# CamLink.net
KiCad netlist of a schematic drawn in Altium Designer
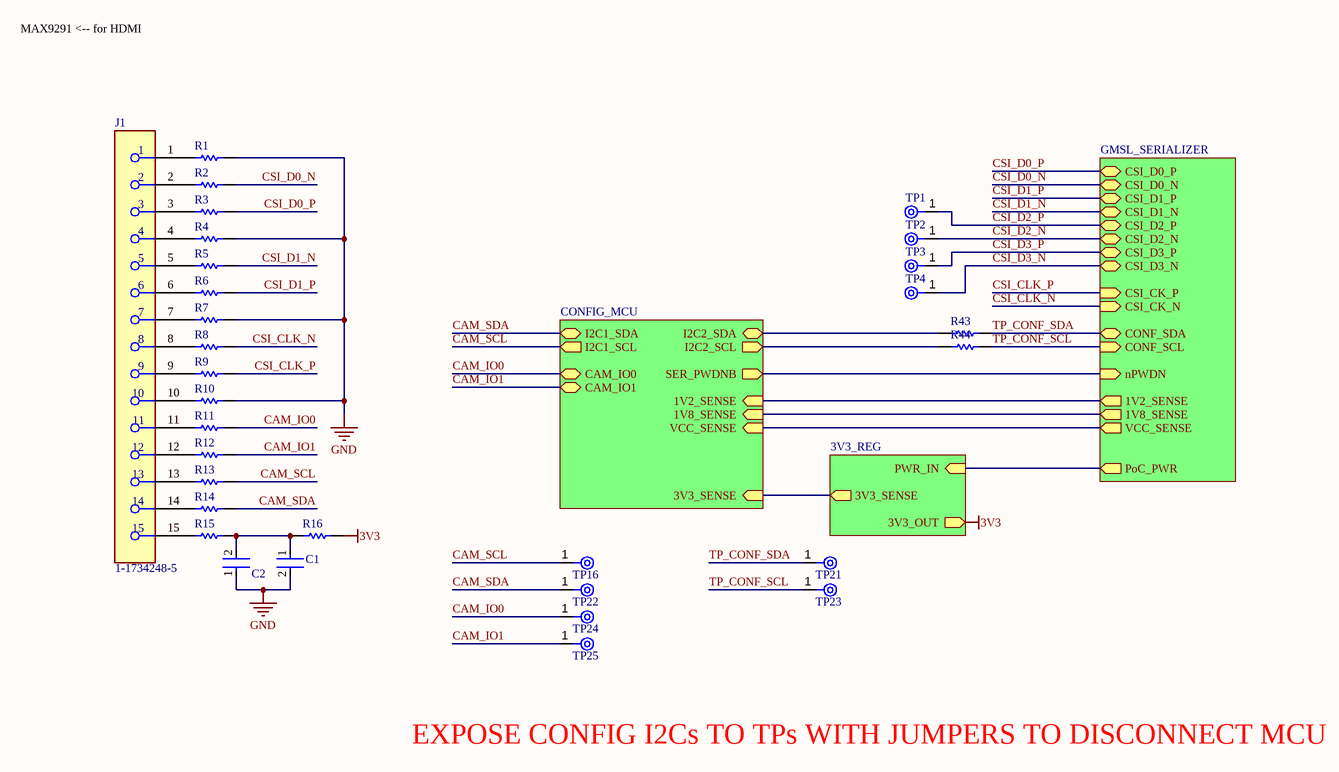
[diagram p0: CamLink.SchDoc]

(export (version "E")
  (design (tool "Eeschema 10.0.6"))
  (components
    (comp (ref "C1")
      (value "CL05A106MP5NUNC")
      (footprint "FP-CL05A106MP5NUNC-MFG")
      (description "CAP CER 10UF 10V X5R 0402")
      (fields
        (field (name "OCTOPART") "https://octopart.com/cl05a106mp5nunc-samsung-22457395")
        (field (name "TOLERANCE") "20%")
      )
      (libsource (lib "Altium Content Vault") (part "b4654b650e69147ec39a6b967a45e02"))
    )
    (comp (ref "C2")
      (value "C1005X7R1H104K050BB")
      (footprint "FP-C1005-050-0_05-IPC_C")
      (description "Multilayer Ceramic Capacitors 100nF ±10% 50V X7R SMD 0402")
      (fields (field (name "VOLTAGE") "50V") (field (name "TOLERANCE") "10%"))
      (libsource (lib "Altium Content Vault") (part "b4654b650e69147ec39a6b967a45e02"))
    )
    (comp (ref "J1")
      (value "1-1734248-5")
      (footprint "FP-1-1734248-5-MFG")
      (description "CONN FPC VERT 15POS 1.00MM SMD")
      (fields
        (field (name "MANUFACTURER") "TE")
        (field (name "OCTOPART") "https://octopart.com/1-1734248-5-te+connectivity-40620898")
      )
      (libsource (lib "Altium Content Vault") (part "a0777be16b290adccad2a8f9338c195"))
    )
    (comp (ref "R1")
      (value "RC0402JR-070RL")
      (footprint "RESC1005X40X25NL05T10")
      (fields (field (name "MANUFACTURER") "Yageo / Phycomp"))
      (libsource (lib "Altium Content Vault") (part "RES"))
    )
    (comp (ref "R2")
      (value "RC0402JR-070RL")
      (footprint "RESC1005X40X25NL05T10")
      (fields (field (name "MANUFACTURER") "Yageo / Phycomp"))
      (libsource (lib "Altium Content Vault") (part "RES"))
    )
    (comp (ref "R3")
      (value "RC0402JR-070RL")
      (footprint "RESC1005X40X25NL05T10")
      (fields (field (name "MANUFACTURER") "Yageo / Phycomp"))
      (libsource (lib "Altium Content Vault") (part "RES"))
    )
    (comp (ref "R4")
      (value "RC0402JR-070RL")
      (footprint "RESC1005X40X25NL05T10")
      (fields (field (name "MANUFACTURER") "Yageo / Phycomp"))
      (libsource (lib "Altium Content Vault") (part "RES"))
    )
    (comp (ref "R5")
      (value "RC0402JR-070RL")
      (footprint "RESC1005X40X25NL05T10")
      (fields (field (name "MANUFACTURER") "Yageo / Phycomp"))
      (libsource (lib "Altium Content Vault") (part "RES"))
    )
    (comp (ref "R6")
      (value "RC0402JR-070RL")
      (footprint "RESC1005X40X25NL05T10")
      (fields (field (name "MANUFACTURER") "Yageo / Phycomp"))
      (libsource (lib "Altium Content Vault") (part "RES"))
    )
    (comp (ref "R7")
      (value "RC0402JR-070RL")
      (footprint "RESC1005X40X25NL05T10")
      (fields (field (name "MANUFACTURER") "Yageo / Phycomp"))
      (libsource (lib "Altium Content Vault") (part "RES"))
    )
    (comp (ref "R8")
      (value "RC0402JR-070RL")
      (footprint "RESC1005X40X25NL05T10")
      (fields (field (name "MANUFACTURER") "Yageo / Phycomp"))
      (libsource (lib "Altium Content Vault") (part "RES"))
    )
    (comp (ref "R9")
      (value "RC0402JR-070RL")
      (footprint "RESC1005X40X25NL05T10")
      (fields (field (name "MANUFACTURER") "Yageo / Phycomp"))
      (libsource (lib "Altium Content Vault") (part "RES"))
    )
    (comp (ref "R10")
      (value "RC0402JR-070RL")
      (footprint "RESC1005X40X25NL05T10")
      (fields (field (name "MANUFACTURER") "Yageo / Phycomp"))
      (libsource (lib "Altium Content Vault") (part "RES"))
    )
    (comp (ref "R11")
      (value "RC0402JR-070RL")
      (footprint "RESC1005X40X25NL05T10")
      (fields (field (name "MANUFACTURER") "Yageo / Phycomp"))
      (libsource (lib "Altium Content Vault") (part "RES"))
    )
    (comp (ref "R12")
      (value "RC0402JR-070RL")
      (footprint "RESC1005X40X25NL05T10")
      (fields (field (name "MANUFACTURER") "Yageo / Phycomp"))
      (libsource (lib "Altium Content Vault") (part "RES"))
    )
    (comp (ref "R13")
      (value "RC0402JR-070RL")
      (footprint "RESC1005X40X25NL05T10")
      (fields (field (name "MANUFACTURER") "Yageo / Phycomp"))
      (libsource (lib "Altium Content Vault") (part "RES"))
    )
    (comp (ref "R14")
      (value "RC0402JR-070RL")
      (footprint "RESC1005X40X25NL05T10")
      (fields (field (name "MANUFACTURER") "Yageo / Phycomp"))
      (libsource (lib "Altium Content Vault") (part "RES"))
    )
    (comp (ref "R15")
      (value "RC0402JR-070RL")
      (footprint "RESC1005X40X25NL05T10")
      (fields (field (name "MANUFACTURER") "Yageo / Phycomp"))
      (libsource (lib "Altium Content Vault") (part "RES"))
    )
    (comp (ref "R16")
      (value "RC0402JR-070RL")
      (footprint "RESC1005X40X25NL05T10")
      (fields (field (name "MANUFACTURER") "Yageo / Phycomp"))
      (libsource (lib "Altium Content Vault") (part "RES"))
    )
    (comp (ref "R43")
      (value "RC0402JR-070RL")
      (footprint "RESC1005X40X25NL05T10")
      (fields (field (name "MANUFACTURER") "Yageo / Phycomp"))
      (libsource (lib "Altium Content Vault") (part "RES"))
    )
    (comp (ref "R44")
      (value "RC0402JR-070RL")
      (footprint "RESC1005X40X25NL05T10")
      (fields (field (name "MANUFACTURER") "Yageo / Phycomp"))
      (libsource (lib "Altium Content Vault") (part "RES"))
    )
    (comp (ref "TP1")
      (value "TPAD6R")
      (footprint "New footprint 1")
      (description "Test Point .6mm")
      (libsource (lib "Space Concordia") (part "TP"))
    )
    (comp (ref "TP2")
      (value "TPAD6R")
      (footprint "New footprint 1")
      (description "Test Point .6mm")
      (libsource (lib "Space Concordia") (part "TP"))
    )
    (comp (ref "TP3")
      (value "TPAD6R")
      (footprint "New footprint 1")
      (description "Test Point .6mm")
      (libsource (lib "Space Concordia") (part "TP"))
    )
    (comp (ref "TP4")
      (value "TPAD6R")
      (footprint "New footprint 1")
      (description "Test Point .6mm")
      (libsource (lib "Space Concordia") (part "TP"))
    )
    (comp (ref "TP16")
      (value "TPAD6R")
      (footprint "New footprint 1")
      (description "Test Point .6mm")
      (libsource (lib "Space Concordia") (part "TP"))
    )
    (comp (ref "TP21")
      (value "TPAD6R")
      (footprint "New footprint 1")
      (description "Test Point .6mm")
      (libsource (lib "Space Concordia") (part "TP"))
    )
    (comp (ref "TP22")
      (value "TPAD6R")
      (footprint "New footprint 1")
      (description "Test Point .6mm")
      (libsource (lib "Space Concordia") (part "TP"))
    )
    (comp (ref "TP23")
      (value "TPAD6R")
      (footprint "New footprint 1")
      (description "Test Point .6mm")
      (libsource (lib "Space Concordia") (part "TP"))
    )
    (comp (ref "TP24")
      (value "TPAD6R")
      (footprint "New footprint 1")
      (description "Test Point .6mm")
      (libsource (lib "Space Concordia") (part "TP"))
    )
    (comp (ref "TP25")
      (value "TPAD6R")
      (footprint "New footprint 1")
      (description "Test Point .6mm")
      (libsource (lib "Space Concordia") (part "TP"))
    )
  )
  (nets
    (net (code "4") (name "/CAM_IO0") (class "Default")
      (node (ref "R11") (pin "2") (pinfunction "2_2") (pintype "passive"))
      (node (ref "TP24") (pin "1") (pinfunction "TP_1") (pintype "passive"))
    )
    (net (code "5") (name "/CAM_IO1") (class "Default")
      (node (ref "R12") (pin "2") (pinfunction "2_2") (pintype "passive"))
      (node (ref "TP25") (pin "1") (pinfunction "TP_1") (pintype "passive"))
    )
    (net (code "6") (name "/CAM_SCL") (class "Default")
      (node (ref "R13") (pin "2") (pinfunction "2_2") (pintype "passive"))
      (node (ref "TP16") (pin "1") (pinfunction "TP_1") (pintype "passive"))
    )
    (net (code "7") (name "/CAM_SDA") (class "Default")
      (node (ref "R14") (pin "2") (pinfunction "2_2") (pintype "passive"))
      (node (ref "TP22") (pin "1") (pinfunction "TP_1") (pintype "passive"))
    )
    (net (code "8") (name "/CSI_CLK_N") (class "Default")
      (node (ref "R8") (pin "2") (pinfunction "2_2") (pintype "passive"))
    )
    (net (code "9") (name "/CSI_CLK_P") (class "Default")
      (node (ref "R9") (pin "2") (pinfunction "2_2") (pintype "passive"))
    )
    (net (code "10") (name "/CSI_D0_N") (class "Default")
      (node (ref "R2") (pin "2") (pinfunction "2_2") (pintype "passive"))
    )
    (net (code "11") (name "/CSI_D0_P") (class "Default")
      (node (ref "R3") (pin "2") (pinfunction "2_2") (pintype "passive"))
    )
    (net (code "12") (name "/CSI_D1_N") (class "Default")
      (node (ref "R5") (pin "2") (pinfunction "2_2") (pintype "passive"))
    )
    (net (code "13") (name "/CSI_D1_P") (class "Default")
      (node (ref "R6") (pin "2") (pinfunction "2_2") (pintype "passive"))
    )
    (net (code "14") (name "/CSI_D2_N") (class "Default")
      (node (ref "TP2") (pin "1") (pinfunction "TP_1") (pintype "passive"))
    )
    (net (code "15") (name "/CSI_D2_P") (class "Default")
      (node (ref "TP1") (pin "1") (pinfunction "TP_1") (pintype "passive"))
    )
    (net (code "16") (name "/CSI_D3_N") (class "Default")
      (node (ref "TP4") (pin "1") (pinfunction "TP_1") (pintype "passive"))
    )
    (net (code "17") (name "/CSI_D3_P") (class "Default")
      (node (ref "TP3") (pin "1") (pinfunction "TP_1") (pintype "passive"))
    )
    (net (code "18") (name "/I2C2_SCL") (class "Default")
      (node (ref "R44") (pin "1") (pinfunction "1_1") (pintype "passive"))
    )
    (net (code "19") (name "/I2C2_SDA") (class "Default")
      (node (ref "R43") (pin "1") (pinfunction "1_1") (pintype "passive"))
    )
    (net (code "22") (name "/TP_CONF_SCL") (class "Default")
      (node (ref "R44") (pin "2") (pinfunction "2_2") (pintype "passive"))
      (node (ref "TP23") (pin "1") (pinfunction "TP_1") (pintype "passive"))
    )
    (net (code "23") (name "/TP_CONF_SDA") (class "Default")
      (node (ref "R43") (pin "2") (pinfunction "2_2") (pintype "passive"))
      (node (ref "TP21") (pin "1") (pinfunction "TP_1") (pintype "passive"))
    )
    (net (code "25") (name "3V3") (class "Default")
      (node (ref "R16") (pin "2") (pinfunction "2_2") (pintype "passive"))
    )
    (net (code "26") (name "GND") (class "Default")
      (node (ref "C1") (pin "2") (pinfunction "2_2") (pintype "passive"))
      (node (ref "C2") (pin "1") (pinfunction "1_1") (pintype "passive"))
      (node (ref "R1") (pin "2") (pinfunction "2_2") (pintype "passive"))
      (node (ref "R10") (pin "2") (pinfunction "2_2") (pintype "passive"))
      (node (ref "R4") (pin "2") (pinfunction "2_2") (pintype "passive"))
      (node (ref "R7") (pin "2") (pinfunction "2_2") (pintype "passive"))
    )
    (net (code "27") (name "Net-(C1-Pad1)") (class "Default")
      (node (ref "C1") (pin "1") (pinfunction "1_1") (pintype "passive"))
      (node (ref "C2") (pin "2") (pinfunction "2_2") (pintype "passive"))
      (node (ref "R15") (pin "2") (pinfunction "2_2") (pintype "passive"))
      (node (ref "R16") (pin "1") (pinfunction "1_1") (pintype "passive"))
    )
    (net (code "28") (name "Net-(J1-Pad1)") (class "Default")
      (node (ref "J1") (pin "1") (pinfunction "1_1") (pintype "passive"))
      (node (ref "R1") (pin "1") (pinfunction "1_1") (pintype "passive"))
    )
    (net (code "29") (name "Net-(J1-Pad2)") (class "Default")
      (node (ref "J1") (pin "2") (pinfunction "2_2") (pintype "passive"))
      (node (ref "R2") (pin "1") (pinfunction "1_1") (pintype "passive"))
    )
    (net (code "30") (name "Net-(J1-Pad3)") (class "Default")
      (node (ref "J1") (pin "3") (pinfunction "3_3") (pintype "passive"))
      (node (ref "R3") (pin "1") (pinfunction "1_1") (pintype "passive"))
    )
    (net (code "31") (name "Net-(J1-Pad4)") (class "Default")
      (node (ref "J1") (pin "4") (pinfunction "4_4") (pintype "passive"))
      (node (ref "R4") (pin "1") (pinfunction "1_1") (pintype "passive"))
    )
    (net (code "32") (name "Net-(J1-Pad5)") (class "Default")
      (node (ref "J1") (pin "5") (pinfunction "5_5") (pintype "passive"))
      (node (ref "R5") (pin "1") (pinfunction "1_1") (pintype "passive"))
    )
    (net (code "33") (name "Net-(J1-Pad6)") (class "Default")
      (node (ref "J1") (pin "6") (pinfunction "6_6") (pintype "passive"))
      (node (ref "R6") (pin "1") (pinfunction "1_1") (pintype "passive"))
    )
    (net (code "34") (name "Net-(J1-Pad7)") (class "Default")
      (node (ref "J1") (pin "7") (pinfunction "7_7") (pintype "passive"))
      (node (ref "R7") (pin "1") (pinfunction "1_1") (pintype "passive"))
    )
    (net (code "35") (name "Net-(J1-Pad8)") (class "Default")
      (node (ref "J1") (pin "8") (pinfunction "8_8") (pintype "passive"))
      (node (ref "R8") (pin "1") (pinfunction "1_1") (pintype "passive"))
    )
    (net (code "36") (name "Net-(J1-Pad9)") (class "Default")
      (node (ref "J1") (pin "9") (pinfunction "9_9") (pintype "passive"))
      (node (ref "R9") (pin "1") (pinfunction "1_1") (pintype "passive"))
    )
    (net (code "37") (name "Net-(J1-Pad10)") (class "Default")
      (node (ref "J1") (pin "10") (pinfunction "10_10") (pintype "passive"))
      (node (ref "R10") (pin "1") (pinfunction "1_1") (pintype "passive"))
    )
    (net (code "38") (name "Net-(J1-Pad11)") (class "Default")
      (node (ref "J1") (pin "11") (pinfunction "11_11") (pintype "passive"))
      (node (ref "R11") (pin "1") (pinfunction "1_1") (pintype "passive"))
    )
    (net (code "39") (name "Net-(J1-Pad12)") (class "Default")
      (node (ref "J1") (pin "12") (pinfunction "12_12") (pintype "passive"))
      (node (ref "R12") (pin "1") (pinfunction "1_1") (pintype "passive"))
    )
    (net (code "40") (name "Net-(J1-Pad13)") (class "Default")
      (node (ref "J1") (pin "13") (pinfunction "13_13") (pintype "passive"))
      (node (ref "R13") (pin "1") (pinfunction "1_1") (pintype "passive"))
    )
    (net (code "41") (name "Net-(J1-Pad14)") (class "Default")
      (node (ref "J1") (pin "14") (pinfunction "14_14") (pintype "passive"))
      (node (ref "R14") (pin "1") (pinfunction "1_1") (pintype "passive"))
    )
    (net (code "42") (name "Net-(J1-Pad15)") (class "Default")
      (node (ref "J1") (pin "15") (pinfunction "15_15") (pintype "passive"))
      (node (ref "R15") (pin "1") (pinfunction "1_1") (pintype "passive"))
    )
  )
)
